# v1_4_button.net
KiCad netlist of a schematic drawn in EAGLE
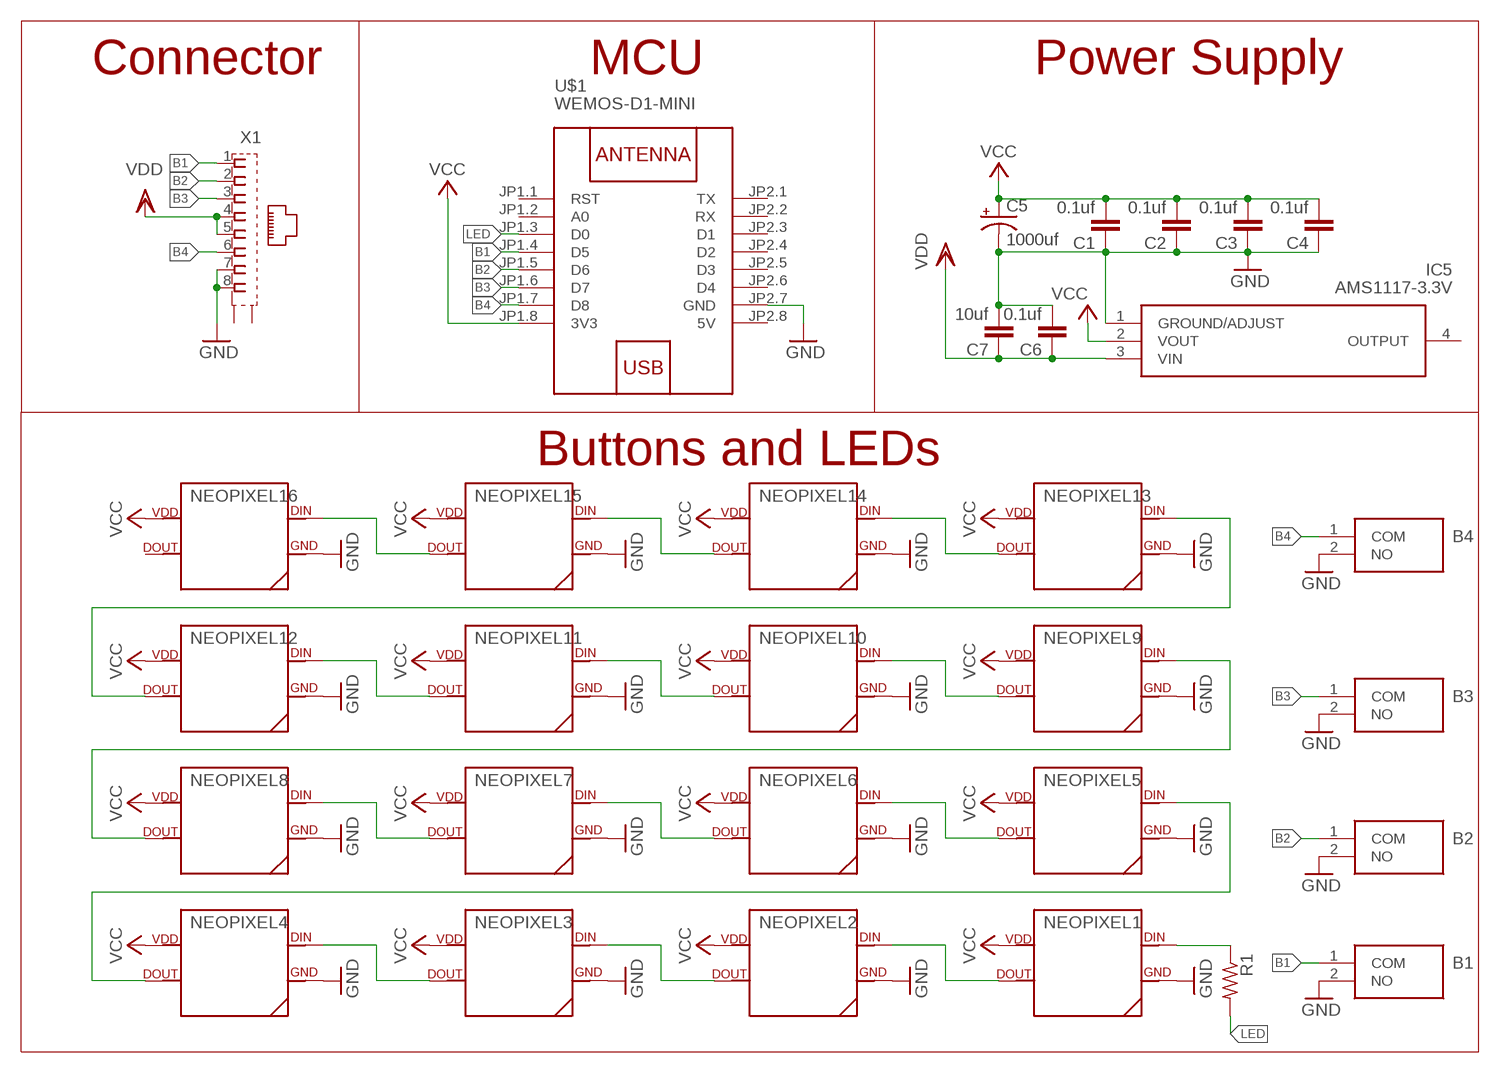
[diagram p0: schematic, sheet 1]

(export (version "E")
  (design (tool "Eeschema 10.0.6"))
  (components
    (comp (ref "B1")
      (value "PTS636_SM25F_SMTR_LFS")
      (footprint "eagle-import:PTS636SM25FSMTRLFS")
      (fields
        (field (name "ARROW_PART_NUMBER") "PTS636 SM25F SMTR LFS")
        (field (name "MOUSER_PART_NUMBER") "611-PTS636SM25FSMTRL")
      )
      (libsource (lib "eagle-import") (part "PTS636_SM25F_SMTR_LFS"))
    )
    (comp (ref "B2")
      (value "PTS636_SM25F_SMTR_LFS")
      (footprint "eagle-import:PTS636SM25FSMTRLFS")
      (fields
        (field (name "ARROW_PART_NUMBER") "PTS636 SM25F SMTR LFS")
        (field (name "MOUSER_PART_NUMBER") "611-PTS636SM25FSMTRL")
      )
      (libsource (lib "eagle-import") (part "PTS636_SM25F_SMTR_LFS"))
    )
    (comp (ref "B3")
      (value "PTS636_SM25F_SMTR_LFS")
      (footprint "eagle-import:PTS636SM25FSMTRLFS")
      (fields
        (field (name "ARROW_PART_NUMBER") "PTS636 SM25F SMTR LFS")
        (field (name "MOUSER_PART_NUMBER") "611-PTS636SM25FSMTRL")
      )
      (libsource (lib "eagle-import") (part "PTS636_SM25F_SMTR_LFS"))
    )
    (comp (ref "B4")
      (value "PTS636_SM25F_SMTR_LFS")
      (footprint "eagle-import:PTS636SM25FSMTRLFS")
      (fields
        (field (name "ARROW_PART_NUMBER") "PTS636 SM25F SMTR LFS")
        (field (name "MOUSER_PART_NUMBER") "611-PTS636SM25FSMTRL")
      )
      (libsource (lib "eagle-import") (part "PTS636_SM25F_SMTR_LFS"))
    )
    (comp (ref "C1")
      (value "0.1uf")
      (footprint "eagle-import:C0603")
      (libsource (lib "eagle-import") (part "C-EUC0603"))
    )
    (comp (ref "C2")
      (value "0.1uf")
      (footprint "eagle-import:C0603")
      (libsource (lib "eagle-import") (part "C-EUC0603"))
    )
    (comp (ref "C3")
      (value "0.1uf")
      (footprint "eagle-import:C0603")
      (libsource (lib "eagle-import") (part "C-EUC0603"))
    )
    (comp (ref "C4")
      (value "0.1uf")
      (footprint "eagle-import:C0603")
      (libsource (lib "eagle-import") (part "C-EUC0603"))
    )
    (comp (ref "C5")
      (value "1000uf")
      (footprint "eagle-import:UD-10X10_NICHICON")
      (libsource (lib "eagle-import") (part "CPOL-USUD-10X10"))
    )
    (comp (ref "C6")
      (value "0.1uf")
      (footprint "eagle-import:C0603")
      (libsource (lib "eagle-import") (part "C-EUC0603"))
    )
    (comp (ref "C7")
      (value "10uf")
      (footprint "eagle-import:C0603")
      (libsource (lib "eagle-import") (part "C-EUC0603"))
    )
    (comp (ref "IC5")
      (value "AMS1117-3.3V")
      (footprint "eagle-import:SOT229P700X180-4N")
      (fields (field (name "MANUFACTURER_PART_NUMBER") "ams1117-3.3v"))
      (libsource (lib "eagle-import") (part "AMS1117-3.3V"))
    )
    (comp (ref "NEOPIXEL1")
      (value "SK6812NEOPIXEL5050")
      (footprint "eagle-import:SK6812")
      (libsource (lib "eagle-import") (part "SK68125050NEOPIXEL"))
    )
    (comp (ref "NEOPIXEL2")
      (value "SK6812NEOPIXEL5050")
      (footprint "eagle-import:SK6812")
      (libsource (lib "eagle-import") (part "SK68125050NEOPIXEL"))
    )
    (comp (ref "NEOPIXEL3")
      (value "SK6812NEOPIXEL5050")
      (footprint "eagle-import:SK6812")
      (libsource (lib "eagle-import") (part "SK68125050NEOPIXEL"))
    )
    (comp (ref "NEOPIXEL4")
      (value "SK6812NEOPIXEL5050")
      (footprint "eagle-import:SK6812")
      (libsource (lib "eagle-import") (part "SK68125050NEOPIXEL"))
    )
    (comp (ref "NEOPIXEL5")
      (value "SK6812NEOPIXEL5050")
      (footprint "eagle-import:SK6812")
      (libsource (lib "eagle-import") (part "SK68125050NEOPIXEL"))
    )
    (comp (ref "NEOPIXEL6")
      (value "SK6812NEOPIXEL5050")
      (footprint "eagle-import:SK6812")
      (libsource (lib "eagle-import") (part "SK68125050NEOPIXEL"))
    )
    (comp (ref "NEOPIXEL7")
      (value "SK6812NEOPIXEL5050")
      (footprint "eagle-import:SK6812")
      (libsource (lib "eagle-import") (part "SK68125050NEOPIXEL"))
    )
    (comp (ref "NEOPIXEL8")
      (value "SK6812NEOPIXEL5050")
      (footprint "eagle-import:SK6812")
      (libsource (lib "eagle-import") (part "SK68125050NEOPIXEL"))
    )
    (comp (ref "NEOPIXEL9")
      (value "SK6812NEOPIXEL5050")
      (footprint "eagle-import:SK6812")
      (libsource (lib "eagle-import") (part "SK68125050NEOPIXEL"))
    )
    (comp (ref "NEOPIXEL10")
      (value "SK6812NEOPIXEL5050")
      (footprint "eagle-import:SK6812")
      (libsource (lib "eagle-import") (part "SK68125050NEOPIXEL"))
    )
    (comp (ref "NEOPIXEL11")
      (value "SK6812NEOPIXEL5050")
      (footprint "eagle-import:SK6812")
      (libsource (lib "eagle-import") (part "SK68125050NEOPIXEL"))
    )
    (comp (ref "NEOPIXEL12")
      (value "SK6812NEOPIXEL5050")
      (footprint "eagle-import:SK6812")
      (libsource (lib "eagle-import") (part "SK68125050NEOPIXEL"))
    )
    (comp (ref "NEOPIXEL13")
      (value "SK6812NEOPIXEL5050")
      (footprint "eagle-import:SK6812")
      (libsource (lib "eagle-import") (part "SK68125050NEOPIXEL"))
    )
    (comp (ref "NEOPIXEL14")
      (value "SK6812NEOPIXEL5050")
      (footprint "eagle-import:SK6812")
      (libsource (lib "eagle-import") (part "SK68125050NEOPIXEL"))
    )
    (comp (ref "NEOPIXEL15")
      (value "SK6812NEOPIXEL5050")
      (footprint "eagle-import:SK6812")
      (libsource (lib "eagle-import") (part "SK68125050NEOPIXEL"))
    )
    (comp (ref "NEOPIXEL16")
      (value "SK6812NEOPIXEL5050")
      (footprint "eagle-import:SK6812")
      (libsource (lib "eagle-import") (part "SK68125050NEOPIXEL"))
    )
    (comp (ref "R1")
      (value "R-US_R0603")
      (footprint "eagle-import:R0603")
      (libsource (lib "eagle-import") (part "R-US_R0603"))
    )
    (comp (ref "U$1")
      (value "WEMOS-D1-MINI")
      (footprint "eagle-import:WEMOS-D1-MINI")
      (libsource (lib "eagle-import") (part "WEMOS-D1-MINI"))
    )
    (comp (ref "X1")
      (value "0446200002")
      (footprint "eagle-import:0446200002")
      (fields (field (name "MF") "MOLEX"))
      (libsource (lib "eagle-import") (part "0446200002"))
    )
  )
  (nets
    (net (code "1") (name "/5V") (class "Default")
      (node (ref "U$1") (pin "JP2.8") (pinfunction "5V_JP2.8") (pintype "power_in"))
    )
    (net (code "2") (name "B1") (class "Default")
      (node (ref "B1") (pin "1") (pinfunction "COM_1") (pintype "bidirectional"))
      (node (ref "U$1") (pin "JP1.4") (pinfunction "D5_JP1.4") (pintype "bidirectional"))
      (node (ref "X1") (pin "1") (pinfunction "1_1") (pintype "passive"))
    )
    (net (code "3") (name "B2") (class "Default")
      (node (ref "B2") (pin "1") (pinfunction "COM_1") (pintype "bidirectional"))
      (node (ref "U$1") (pin "JP1.5") (pinfunction "D6_JP1.5") (pintype "bidirectional"))
      (node (ref "X1") (pin "2") (pinfunction "2_2") (pintype "passive"))
    )
    (net (code "4") (name "B3") (class "Default")
      (node (ref "B3") (pin "1") (pinfunction "COM_1") (pintype "bidirectional"))
      (node (ref "U$1") (pin "JP1.6") (pinfunction "D7_JP1.6") (pintype "bidirectional"))
      (node (ref "X1") (pin "3") (pinfunction "3_3") (pintype "passive"))
    )
    (net (code "5") (name "B4") (class "Default")
      (node (ref "B4") (pin "1") (pinfunction "COM_1") (pintype "bidirectional"))
      (node (ref "U$1") (pin "JP1.7") (pinfunction "D8_JP1.7") (pintype "bidirectional"))
      (node (ref "X1") (pin "6") (pinfunction "6_6") (pintype "passive"))
    )
    (net (code "6") (name "GND") (class "Default")
      (node (ref "B1") (pin "2") (pinfunction "NO_2") (pintype "bidirectional"))
      (node (ref "B2") (pin "2") (pinfunction "NO_2") (pintype "bidirectional"))
      (node (ref "B3") (pin "2") (pinfunction "NO_2") (pintype "bidirectional"))
      (node (ref "B4") (pin "2") (pinfunction "NO_2") (pintype "bidirectional"))
      (node (ref "C1") (pin "1") (pinfunction "1_1") (pintype "passive"))
      (node (ref "C2") (pin "1") (pinfunction "1_1") (pintype "passive"))
      (node (ref "C3") (pin "1") (pinfunction "1_1") (pintype "passive"))
      (node (ref "C4") (pin "1") (pinfunction "1_1") (pintype "passive"))
      (node (ref "C5") (pin "-") (pinfunction "-_-") (pintype "passive"))
      (node (ref "C6") (pin "2") (pinfunction "2_2") (pintype "passive"))
      (node (ref "C7") (pin "2") (pinfunction "2_2") (pintype "passive"))
      (node (ref "IC5") (pin "1") (pinfunction "GROUND/ADJUST_1") (pintype "bidirectional"))
      (node (ref "NEOPIXEL1") (pin "3") (pinfunction "GND_3") (pintype "bidirectional"))
      (node (ref "NEOPIXEL10") (pin "3") (pinfunction "GND_3") (pintype "bidirectional"))
      (node (ref "NEOPIXEL11") (pin "3") (pinfunction "GND_3") (pintype "bidirectional"))
      (node (ref "NEOPIXEL12") (pin "3") (pinfunction "GND_3") (pintype "bidirectional"))
      (node (ref "NEOPIXEL13") (pin "3") (pinfunction "GND_3") (pintype "bidirectional"))
      (node (ref "NEOPIXEL14") (pin "3") (pinfunction "GND_3") (pintype "bidirectional"))
      (node (ref "NEOPIXEL15") (pin "3") (pinfunction "GND_3") (pintype "bidirectional"))
      (node (ref "NEOPIXEL16") (pin "3") (pinfunction "GND_3") (pintype "bidirectional"))
      (node (ref "NEOPIXEL2") (pin "3") (pinfunction "GND_3") (pintype "bidirectional"))
      (node (ref "NEOPIXEL3") (pin "3") (pinfunction "GND_3") (pintype "bidirectional"))
      (node (ref "NEOPIXEL4") (pin "3") (pinfunction "GND_3") (pintype "bidirectional"))
      (node (ref "NEOPIXEL5") (pin "3") (pinfunction "GND_3") (pintype "bidirectional"))
      (node (ref "NEOPIXEL6") (pin "3") (pinfunction "GND_3") (pintype "bidirectional"))
      (node (ref "NEOPIXEL7") (pin "3") (pinfunction "GND_3") (pintype "bidirectional"))
      (node (ref "NEOPIXEL8") (pin "3") (pinfunction "GND_3") (pintype "bidirectional"))
      (node (ref "NEOPIXEL9") (pin "3") (pinfunction "GND_3") (pintype "bidirectional"))
      (node (ref "U$1") (pin "JP2.7") (pinfunction "GND_JP2.7") (pintype "power_in"))
      (node (ref "X1") (pin "7") (pinfunction "7_7") (pintype "passive"))
      (node (ref "X1") (pin "8") (pinfunction "8_8") (pintype "passive"))
    )
    (net (code "7") (name "LED") (class "Default")
      (node (ref "R1") (pin "2") (pinfunction "2_2") (pintype "passive"))
      (node (ref "U$1") (pin "JP1.3") (pinfunction "D0_JP1.3") (pintype "bidirectional"))
    )
    (net (code "8") (name "Net-(NEOPIXEL1-DIN)") (class "Default")
      (node (ref "NEOPIXEL1") (pin "4") (pinfunction "DIN_4") (pintype "bidirectional"))
      (node (ref "R1") (pin "1") (pinfunction "1_1") (pintype "passive"))
    )
    (net (code "9") (name "Net-(NEOPIXEL1-DOUT)") (class "Default")
      (node (ref "NEOPIXEL1") (pin "2") (pinfunction "DOUT_2") (pintype "bidirectional"))
      (node (ref "NEOPIXEL2") (pin "4") (pinfunction "DIN_4") (pintype "bidirectional"))
    )
    (net (code "10") (name "Net-(NEOPIXEL2-DOUT)") (class "Default")
      (node (ref "NEOPIXEL2") (pin "2") (pinfunction "DOUT_2") (pintype "bidirectional"))
      (node (ref "NEOPIXEL3") (pin "4") (pinfunction "DIN_4") (pintype "bidirectional"))
    )
    (net (code "11") (name "Net-(NEOPIXEL3-DOUT)") (class "Default")
      (node (ref "NEOPIXEL3") (pin "2") (pinfunction "DOUT_2") (pintype "bidirectional"))
      (node (ref "NEOPIXEL4") (pin "4") (pinfunction "DIN_4") (pintype "bidirectional"))
    )
    (net (code "12") (name "Net-(NEOPIXEL4-DOUT)") (class "Default")
      (node (ref "NEOPIXEL4") (pin "2") (pinfunction "DOUT_2") (pintype "bidirectional"))
      (node (ref "NEOPIXEL5") (pin "4") (pinfunction "DIN_4") (pintype "bidirectional"))
    )
    (net (code "13") (name "Net-(NEOPIXEL5-DOUT)") (class "Default")
      (node (ref "NEOPIXEL5") (pin "2") (pinfunction "DOUT_2") (pintype "bidirectional"))
      (node (ref "NEOPIXEL6") (pin "4") (pinfunction "DIN_4") (pintype "bidirectional"))
    )
    (net (code "14") (name "Net-(NEOPIXEL6-DOUT)") (class "Default")
      (node (ref "NEOPIXEL6") (pin "2") (pinfunction "DOUT_2") (pintype "bidirectional"))
      (node (ref "NEOPIXEL7") (pin "4") (pinfunction "DIN_4") (pintype "bidirectional"))
    )
    (net (code "15") (name "Net-(NEOPIXEL7-DOUT)") (class "Default")
      (node (ref "NEOPIXEL7") (pin "2") (pinfunction "DOUT_2") (pintype "bidirectional"))
      (node (ref "NEOPIXEL8") (pin "4") (pinfunction "DIN_4") (pintype "bidirectional"))
    )
    (net (code "16") (name "Net-(NEOPIXEL8-DOUT)") (class "Default")
      (node (ref "NEOPIXEL8") (pin "2") (pinfunction "DOUT_2") (pintype "bidirectional"))
      (node (ref "NEOPIXEL9") (pin "4") (pinfunction "DIN_4") (pintype "bidirectional"))
    )
    (net (code "17") (name "Net-(NEOPIXEL10-DIN)") (class "Default")
      (node (ref "NEOPIXEL10") (pin "4") (pinfunction "DIN_4") (pintype "bidirectional"))
      (node (ref "NEOPIXEL9") (pin "2") (pinfunction "DOUT_2") (pintype "bidirectional"))
    )
    (net (code "18") (name "Net-(NEOPIXEL10-DOUT)") (class "Default")
      (node (ref "NEOPIXEL10") (pin "2") (pinfunction "DOUT_2") (pintype "bidirectional"))
      (node (ref "NEOPIXEL11") (pin "4") (pinfunction "DIN_4") (pintype "bidirectional"))
    )
    (net (code "19") (name "Net-(NEOPIXEL11-DOUT)") (class "Default")
      (node (ref "NEOPIXEL11") (pin "2") (pinfunction "DOUT_2") (pintype "bidirectional"))
      (node (ref "NEOPIXEL12") (pin "4") (pinfunction "DIN_4") (pintype "bidirectional"))
    )
    (net (code "20") (name "Net-(NEOPIXEL12-DOUT)") (class "Default")
      (node (ref "NEOPIXEL12") (pin "2") (pinfunction "DOUT_2") (pintype "bidirectional"))
      (node (ref "NEOPIXEL13") (pin "4") (pinfunction "DIN_4") (pintype "bidirectional"))
    )
    (net (code "21") (name "Net-(NEOPIXEL13-DOUT)") (class "Default")
      (node (ref "NEOPIXEL13") (pin "2") (pinfunction "DOUT_2") (pintype "bidirectional"))
      (node (ref "NEOPIXEL14") (pin "4") (pinfunction "DIN_4") (pintype "bidirectional"))
    )
    (net (code "22") (name "Net-(NEOPIXEL14-DOUT)") (class "Default")
      (node (ref "NEOPIXEL14") (pin "2") (pinfunction "DOUT_2") (pintype "bidirectional"))
      (node (ref "NEOPIXEL15") (pin "4") (pinfunction "DIN_4") (pintype "bidirectional"))
    )
    (net (code "23") (name "Net-(NEOPIXEL15-DOUT)") (class "Default")
      (node (ref "NEOPIXEL15") (pin "2") (pinfunction "DOUT_2") (pintype "bidirectional"))
      (node (ref "NEOPIXEL16") (pin "4") (pinfunction "DIN_4") (pintype "bidirectional"))
    )
    (net (code "24") (name "VCC") (class "Default")
      (node (ref "C1") (pin "2") (pinfunction "2_2") (pintype "passive"))
      (node (ref "C2") (pin "2") (pinfunction "2_2") (pintype "passive"))
      (node (ref "C3") (pin "2") (pinfunction "2_2") (pintype "passive"))
      (node (ref "C4") (pin "2") (pinfunction "2_2") (pintype "passive"))
      (node (ref "C5") (pin "+") (pinfunction "+_+") (pintype "passive"))
      (node (ref "IC5") (pin "2") (pinfunction "VOUT_2") (pintype "bidirectional"))
      (node (ref "NEOPIXEL1") (pin "1") (pinfunction "VDD_1") (pintype "bidirectional"))
      (node (ref "NEOPIXEL10") (pin "1") (pinfunction "VDD_1") (pintype "bidirectional"))
      (node (ref "NEOPIXEL11") (pin "1") (pinfunction "VDD_1") (pintype "bidirectional"))
      (node (ref "NEOPIXEL12") (pin "1") (pinfunction "VDD_1") (pintype "bidirectional"))
      (node (ref "NEOPIXEL13") (pin "1") (pinfunction "VDD_1") (pintype "bidirectional"))
      (node (ref "NEOPIXEL14") (pin "1") (pinfunction "VDD_1") (pintype "bidirectional"))
      (node (ref "NEOPIXEL15") (pin "1") (pinfunction "VDD_1") (pintype "bidirectional"))
      (node (ref "NEOPIXEL16") (pin "1") (pinfunction "VDD_1") (pintype "bidirectional"))
      (node (ref "NEOPIXEL2") (pin "1") (pinfunction "VDD_1") (pintype "bidirectional"))
      (node (ref "NEOPIXEL3") (pin "1") (pinfunction "VDD_1") (pintype "bidirectional"))
      (node (ref "NEOPIXEL4") (pin "1") (pinfunction "VDD_1") (pintype "bidirectional"))
      (node (ref "NEOPIXEL5") (pin "1") (pinfunction "VDD_1") (pintype "bidirectional"))
      (node (ref "NEOPIXEL6") (pin "1") (pinfunction "VDD_1") (pintype "bidirectional"))
      (node (ref "NEOPIXEL7") (pin "1") (pinfunction "VDD_1") (pintype "bidirectional"))
      (node (ref "NEOPIXEL8") (pin "1") (pinfunction "VDD_1") (pintype "bidirectional"))
      (node (ref "NEOPIXEL9") (pin "1") (pinfunction "VDD_1") (pintype "bidirectional"))
      (node (ref "U$1") (pin "JP1.8") (pinfunction "3V3_JP1.8") (pintype "power_in"))
    )
    (net (code "25") (name "VDD") (class "Default")
      (node (ref "C6") (pin "1") (pinfunction "1_1") (pintype "passive"))
      (node (ref "C7") (pin "1") (pinfunction "1_1") (pintype "passive"))
      (node (ref "IC5") (pin "3") (pinfunction "VIN_3") (pintype "bidirectional"))
      (node (ref "X1") (pin "4") (pinfunction "4_4") (pintype "passive"))
      (node (ref "X1") (pin "5") (pinfunction "5_5") (pintype "passive"))
    )
    (net (code "26") (name "unconnected-(IC5-OUTPUT-Pad4)") (class "Default")
      (node (ref "IC5") (pin "4") (pinfunction "OUTPUT_4") (pintype "bidirectional"))
    )
    (net (code "27") (name "unconnected-(NEOPIXEL16-DOUT-Pad2)") (class "Default")
      (node (ref "NEOPIXEL16") (pin "2") (pinfunction "DOUT_2") (pintype "bidirectional"))
    )
    (net (code "28") (name "unconnected-(U$1-A0-PadJP1.2)") (class "Default")
      (node (ref "U$1") (pin "JP1.2") (pinfunction "A0_JP1.2") (pintype "bidirectional"))
    )
    (net (code "29") (name "unconnected-(U$1-D1-PadJP2.3)") (class "Default")
      (node (ref "U$1") (pin "JP2.3") (pinfunction "D1_JP2.3") (pintype "bidirectional"))
    )
    (net (code "30") (name "unconnected-(U$1-D2-PadJP2.4)") (class "Default")
      (node (ref "U$1") (pin "JP2.4") (pinfunction "D2_JP2.4") (pintype "bidirectional"))
    )
    (net (code "31") (name "unconnected-(U$1-D3-PadJP2.5)") (class "Default")
      (node (ref "U$1") (pin "JP2.5") (pinfunction "D3_JP2.5") (pintype "bidirectional"))
    )
    (net (code "32") (name "unconnected-(U$1-D4-PadJP2.6)") (class "Default")
      (node (ref "U$1") (pin "JP2.6") (pinfunction "D4_JP2.6") (pintype "bidirectional"))
    )
    (net (code "33") (name "unconnected-(U$1-RST-PadJP1.1)") (class "Default")
      (node (ref "U$1") (pin "JP1.1") (pinfunction "RST_JP1.1") (pintype "bidirectional"))
    )
    (net (code "34") (name "unconnected-(U$1-RX-PadJP2.2)") (class "Default")
      (node (ref "U$1") (pin "JP2.2") (pinfunction "RX_JP2.2") (pintype "bidirectional"))
    )
    (net (code "35") (name "unconnected-(U$1-TX-PadJP2.1)") (class "Default")
      (node (ref "U$1") (pin "JP2.1") (pinfunction "TX_JP2.1") (pintype "bidirectional"))
    )
    (net (code "36") (name "unconnected-(X1-S1-PadS@1)") (class "Default")
      (node (ref "X1") (pin "S@1") (pinfunction "S1_S@1") (pintype "passive"))
    )
    (net (code "37") (name "unconnected-(X1-S2-PadS@2)") (class "Default")
      (node (ref "X1") (pin "S@2") (pinfunction "S2_S@2") (pintype "passive"))
    )
  )
)
